# AD8367_AGC.net
KiCad netlist of a schematic drawn in Altium Designer
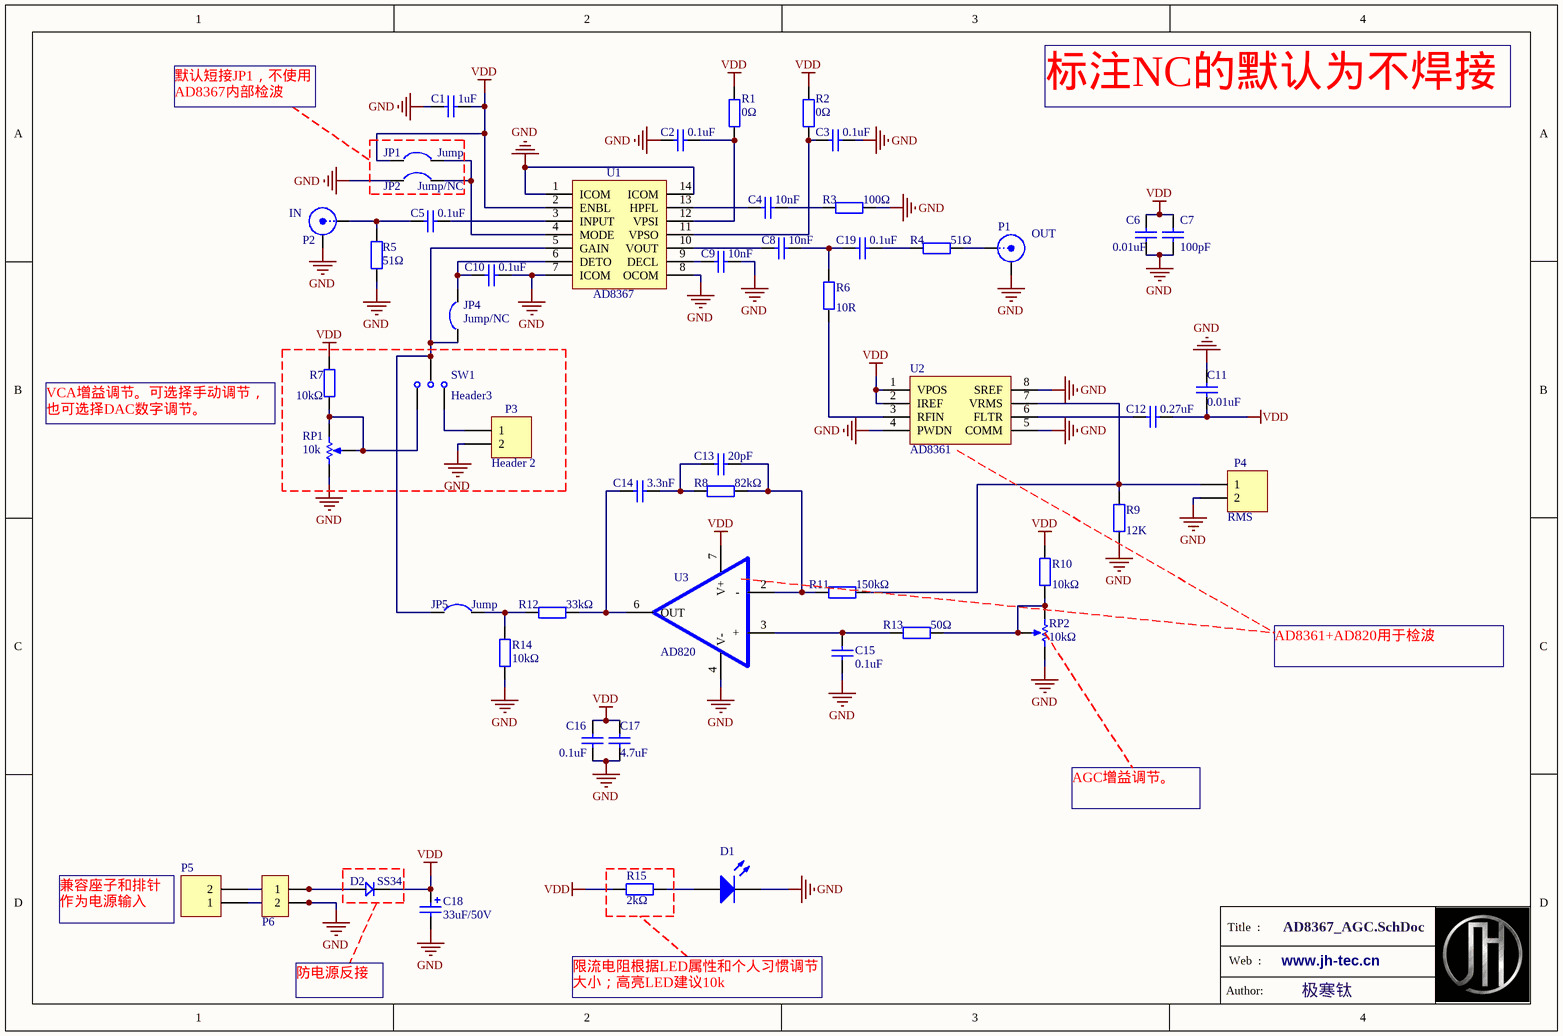
[diagram p0: AD8367_AGC.SchDoc]

(export (version "E")
  (design (tool "Eeschema 10.0.6"))
  (components
    (comp (ref "C1")
      (value "1uF")
      (footprint "JH_PCB:C0603")
      (description "Capacitor (Semiconductor SIM Model)")
      (fields (field (name "PUBLISHER") "Altium Limited"))
      (libsource (lib "mylib") (part "Cap Semi"))
    )
    (comp (ref "C2")
      (value "0.1uF")
      (footprint "JH_PCB:C0603")
      (description "Capacitor (Semiconductor SIM Model)")
      (fields (field (name "PUBLISHER") "Altium Limited"))
      (libsource (lib "mylib") (part "Cap Semi"))
    )
    (comp (ref "C3")
      (value "0.1uF")
      (footprint "JH_PCB:C0603")
      (description "Capacitor (Semiconductor SIM Model)")
      (fields (field (name "PUBLISHER") "Altium Limited"))
      (libsource (lib "mylib") (part "Cap Semi"))
    )
    (comp (ref "C4")
      (value "10nF")
      (footprint "JH_PCB:C0603")
      (description "Capacitor (Semiconductor SIM Model)")
      (fields (field (name "PUBLISHER") "Altium Limited"))
      (libsource (lib "mylib") (part "Cap Semi"))
    )
    (comp (ref "C5")
      (value "0.1uF")
      (footprint "JH_PCB:C0603")
      (description "Capacitor (Semiconductor SIM Model)")
      (fields (field (name "PUBLISHER") "Altium Limited"))
      (libsource (lib "mylib") (part "Cap Semi"))
    )
    (comp (ref "C6")
      (value "0.01uF")
      (footprint "JH_PCB:C0603")
      (description "Capacitor (Semiconductor SIM Model)")
      (fields (field (name "PUBLISHER") "Altium Limited"))
      (libsource (lib "mylib") (part "Cap Semi"))
    )
    (comp (ref "C7")
      (value "100pF")
      (footprint "JH_PCB:C0603")
      (description "Capacitor (Semiconductor SIM Model)")
      (fields (field (name "PUBLISHER") "Altium Limited"))
      (libsource (lib "mylib") (part "Cap Semi"))
    )
    (comp (ref "C8")
      (value "10nF")
      (footprint "JH_PCB:C0603")
      (description "Capacitor (Semiconductor SIM Model)")
      (fields (field (name "PUBLISHER") "Altium Limited"))
      (libsource (lib "mylib") (part "Cap Semi"))
    )
    (comp (ref "C9")
      (value "10nF")
      (footprint "JH_PCB:C0603")
      (description "Capacitor (Semiconductor SIM Model)")
      (fields (field (name "PUBLISHER") "Altium Limited"))
      (libsource (lib "mylib") (part "Cap Semi"))
    )
    (comp (ref "C10")
      (value "0.1uF")
      (footprint "JH_PCB:C0603")
      (description "Capacitor (Semiconductor SIM Model)")
      (fields (field (name "PUBLISHER") "Altium Limited"))
      (libsource (lib "mylib") (part "Cap Semi"))
    )
    (comp (ref "C11")
      (value "0.01uF")
      (footprint "JH_PCB:C0603")
      (description "Capacitor (Semiconductor SIM Model)")
      (fields (field (name "PUBLISHER") "Altium Limited"))
      (libsource (lib "mylib") (part "Cap Semi"))
    )
    (comp (ref "C12")
      (value "0.27uF")
      (footprint "JH_PCB:C0603")
      (description "Capacitor (Semiconductor SIM Model)")
      (fields (field (name "PUBLISHER") "Altium Limited"))
      (libsource (lib "mylib") (part "Cap Semi"))
    )
    (comp (ref "C13")
      (value "20pF")
      (footprint "JH_PCB:C0603")
      (description "Capacitor (Semiconductor SIM Model)")
      (fields (field (name "PUBLISHER") "Altium Limited"))
      (libsource (lib "mylib") (part "Cap Semi"))
    )
    (comp (ref "C14")
      (value "3.3nF")
      (footprint "JH_PCB:C0603")
      (description "Capacitor (Semiconductor SIM Model)")
      (fields (field (name "PUBLISHER") "Altium Limited"))
      (libsource (lib "mylib") (part "Cap Semi"))
    )
    (comp (ref "C15")
      (value "0.1uF")
      (footprint "JH_PCB:C0603")
      (description "Capacitor (Semiconductor SIM Model)")
      (fields (field (name "PUBLISHER") "Altium Limited"))
      (libsource (lib "mylib") (part "Cap Semi"))
    )
    (comp (ref "C16")
      (value "0.1uF")
      (footprint "JH_PCB:C0603")
      (description "Capacitor (Semiconductor SIM Model)")
      (fields (field (name "PUBLISHER") "Altium Limited"))
      (libsource (lib "mylib") (part "Cap Semi"))
    )
    (comp (ref "C17")
      (value "4.7uF")
      (footprint "JH_PCB:C0805")
      (description "Capacitor (Semiconductor SIM Model)")
      (fields (field (name "PUBLISHER") "Altium Limited"))
      (libsource (lib "mylib") (part "Cap Semi"))
    )
    (comp (ref "C18")
      (value "33uF/50V")
      (footprint "JH_PCB:C6.3*7.7")
      (description "Polarized Capacitor (Surface Mount)")
      (fields (field (name "PUBLISHER") "Altium Limited"))
      (libsource (lib "mylib") (part "Cap Pol3_1"))
    )
    (comp (ref "C19")
      (value "0.1uF")
      (footprint "JH_PCB:C0603")
      (description "Capacitor (Semiconductor SIM Model)")
      (fields (field (name "PUBLISHER") "Altium Limited"))
      (libsource (lib "mylib") (part "Cap Semi"))
    )
    (comp (ref "D1")
      (value "LED3")
      (footprint "JH_PCB:LED_GREEN_0603")
      (description "Typical BLUE SiC LED")
      (fields (field (name "PUBLISHER") "Altium Limited"))
      (libsource (lib "mylib") (part "LED3"))
    )
    (comp (ref "D2")
      (value "SS34")
      (footprint "JH_PCB:DO-214AC")
      (description "1N4148")
      (libsource (lib "ATK-SIM900A") (part "D"))
    )
    (comp (ref "JP1") (value "Jump") (footprint "JH_PCB:JUMP") (libsource (lib "") (part "Jump_1")))
    (comp (ref "JP2") (value "Jump/NC") (footprint "JH_PCB:JUMP") (libsource (lib "") (part "Jump_1")))
    (comp (ref "JP4") (value "Jump/NC") (footprint "JH_PCB:JUMP") (libsource (lib "常用sch") (part "Jump")))
    (comp (ref "JP5") (value "Jump") (footprint "JH_PCB:JUMP") (libsource (lib "") (part "Jump_1")))
    (comp (ref "P1") (value "OUT") (footprint "JH_PCB:SMA_3D") (libsource (lib "常用sch") (part "SMA")))
    (comp (ref "P2") (value "IN") (footprint "JH_PCB:SMA_3D") (libsource (lib "常用sch") (part "SMA")))
    (comp (ref "P3")
      (value "Header 2")
      (footprint "JH_PCB:HDR1X2")
      (description "Header, 2-Pin")
      (fields (field (name "PUBLISHER") "Altium Limited"))
      (libsource (lib "Miscellaneous Connectors") (part "Header 2"))
    )
    (comp (ref "P4")
      (value "RMS")
      (footprint "JH_PCB:HDR1X2")
      (description "Header, 2-Pin")
      (fields (field (name "PUBLISHER") "Altium Limited"))
      (libsource (lib "Miscellaneous Connectors") (part "Header 2"))
    )
    (comp (ref "P5")
      (value "~")
      (footprint "JH_PCB:HDR1X2")
      (description "Header, 2-Pin")
      (fields (field (name "PUBLISHER") "Altium Limited"))
      (libsource (lib "") (part "Header 2_1"))
    )
    (comp (ref "P6")
      (value "HDR-1X2")
      (footprint "VH3.96-LI-2P")
      (description "2P接插件")
      (fields (field (name "版权归属") "源创客"))
      (libsource (lib "4.8   - 接插件-脚距3.96") (part "Header 2"))
    )
    (comp (ref "R1")
      (value "0Ω")
      (footprint "JH_PCB:R0603")
      (description "Resistor")
      (fields (field (name "PUBLISHER") "Altium Limited"))
      (libsource (lib "") (part "Res2_1"))
    )
    (comp (ref "R2")
      (value "0Ω")
      (footprint "JH_PCB:R0603")
      (description "Resistor")
      (fields (field (name "PUBLISHER") "Altium Limited"))
      (libsource (lib "") (part "Res2_1"))
    )
    (comp (ref "R3")
      (value "100Ω")
      (footprint "JH_PCB:R0603")
      (description "Resistor")
      (fields (field (name "PUBLISHER") "Altium Limited"))
      (libsource (lib "Miscellaneous Devices") (part "Res2"))
    )
    (comp (ref "R4")
      (value "51Ω")
      (footprint "JH_PCB:R0603")
      (description "Resistor")
      (fields (field (name "PUBLISHER") "Altium Limited"))
      (libsource (lib "Miscellaneous Devices") (part "Res2"))
    )
    (comp (ref "R5")
      (value "51Ω")
      (footprint "JH_PCB:R0603")
      (description "Resistor")
      (fields (field (name "PUBLISHER") "Altium Limited"))
      (libsource (lib "") (part "Res2_1"))
    )
    (comp (ref "R6")
      (value "10R")
      (footprint "JH_PCB:R0603")
      (description "Resistor")
      (fields (field (name "PUBLISHER") "Altium Limited"))
      (libsource (lib "") (part "Res2_1"))
    )
    (comp (ref "R7")
      (value "10kΩ")
      (footprint "JH_PCB:R0603")
      (description "Resistor")
      (fields (field (name "PUBLISHER") "Altium Limited"))
      (libsource (lib "") (part "Res2_1"))
    )
    (comp (ref "R8")
      (value "82kΩ")
      (footprint "JH_PCB:R0603")
      (description "Resistor")
      (fields (field (name "PUBLISHER") "Altium Limited"))
      (libsource (lib "Miscellaneous Devices") (part "Res2"))
    )
    (comp (ref "R9")
      (value "12K")
      (footprint "JH_PCB:R0603")
      (description "Resistor")
      (fields (field (name "PUBLISHER") "Altium Limited"))
      (libsource (lib "") (part "Res2_1"))
    )
    (comp (ref "R10")
      (value "10kΩ")
      (footprint "JH_PCB:R0603")
      (description "Resistor")
      (fields (field (name "PUBLISHER") "Altium Limited"))
      (libsource (lib "") (part "Res2_1"))
    )
    (comp (ref "R11")
      (value "150kΩ")
      (footprint "JH_PCB:R0603")
      (description "Resistor")
      (fields (field (name "PUBLISHER") "Altium Limited"))
      (libsource (lib "Miscellaneous Devices") (part "Res2"))
    )
    (comp (ref "R12")
      (value "33kΩ")
      (footprint "JH_PCB:R0603")
      (description "Resistor")
      (fields (field (name "PUBLISHER") "Altium Limited"))
      (libsource (lib "Miscellaneous Devices") (part "Res2"))
    )
    (comp (ref "R13")
      (value "50Ω")
      (footprint "JH_PCB:R0603")
      (description "Resistor")
      (fields (field (name "PUBLISHER") "Altium Limited"))
      (libsource (lib "Miscellaneous Devices") (part "Res2"))
    )
    (comp (ref "R14")
      (value "10kΩ")
      (footprint "JH_PCB:R0603")
      (description "Resistor")
      (fields (field (name "PUBLISHER") "Altium Limited"))
      (libsource (lib "") (part "Res2_1"))
    )
    (comp (ref "R15")
      (value "2kΩ")
      (footprint "JH_PCB:R0603")
      (description "Resistor")
      (fields (field (name "PUBLISHER") "Altium Limited"))
      (libsource (lib "") (part "Res2_2"))
    )
    (comp (ref "RP1") (value "10k") (footprint "RP_3296W") (libsource (lib "常用sch") (part "SW_A")))
    (comp (ref "RP2") (value "10kΩ") (footprint "RP_3296W") (libsource (lib "常用sch") (part "SW_A")))
    (comp (ref "SW1") (value "Header3") (footprint "JH_PCB:HDR1X3") (libsource (lib "常用sch") (part "SW")))
    (comp (ref "U1") (value "AD8367") (footprint "JH_PCB:TSSOP14") (libsource (lib "常用sch") (part "AD8367")))
    (comp (ref "U2") (value "AD8361") (footprint "JH_PCB:MSOP8") (libsource (lib "常用sch") (part "AD8361")))
    (comp (ref "U3") (value "AD820") (footprint "JH_PCB:SOP-8") (libsource (lib "常用sch") (part "单运放1")))
  )
  (nets
    (net (code "1") (name "GND") (class "Default")
      (node (ref "C1") (pin "1") (pinfunction "1_1") (pintype "passive"))
      (node (ref "C10") (pin "2") (pinfunction "2_2") (pintype "passive"))
      (node (ref "C11") (pin "2") (pinfunction "2_2") (pintype "passive"))
      (node (ref "C15") (pin "2") (pinfunction "2_2") (pintype "passive"))
      (node (ref "C16") (pin "2") (pinfunction "2_2") (pintype "passive"))
      (node (ref "C17") (pin "1") (pinfunction "1_1") (pintype "passive"))
      (node (ref "C18") (pin "2") (pinfunction "2_2") (pintype "passive"))
      (node (ref "C2") (pin "1") (pinfunction "1_1") (pintype "passive"))
      (node (ref "C3") (pin "1") (pinfunction "1_1") (pintype "passive"))
      (node (ref "C6") (pin "2") (pinfunction "2_2") (pintype "passive"))
      (node (ref "C7") (pin "2") (pinfunction "2_2") (pintype "passive"))
      (node (ref "C9") (pin "2") (pinfunction "2_2") (pintype "passive"))
      (node (ref "D1") (pin "2") (pinfunction "K_2") (pintype "passive"))
      (node (ref "JP2") (pin "1") (pinfunction "1_1") (pintype "passive"))
      (node (ref "P1") (pin "2") (pinfunction "Y_2") (pintype "passive"))
      (node (ref "P2") (pin "2") (pinfunction "Y_2") (pintype "passive"))
      (node (ref "P3") (pin "2") (pinfunction "2_2") (pintype "passive"))
      (node (ref "P4") (pin "2") (pinfunction "2_2") (pintype "passive"))
      (node (ref "P5") (pin "1") (pinfunction "1_1") (pintype "passive"))
      (node (ref "P6") (pin "2") (pinfunction "2_2") (pintype "passive"))
      (node (ref "R14") (pin "2") (pinfunction "2_2") (pintype "passive"))
      (node (ref "R3") (pin "2") (pinfunction "2_2") (pintype "passive"))
      (node (ref "R5") (pin "2") (pinfunction "2_2") (pintype "passive"))
      (node (ref "R9") (pin "2") (pinfunction "2_2") (pintype "passive"))
      (node (ref "RP1") (pin "1") (pinfunction "TOP_1") (pintype "passive"))
      (node (ref "RP2") (pin "3") (pinfunction "BOT_3") (pintype "passive"))
      (node (ref "U1") (pin "1") (pinfunction "ICOM_1") (pintype "passive"))
      (node (ref "U1") (pin "14") (pinfunction "ICOM_14") (pintype "passive"))
      (node (ref "U1") (pin "7") (pinfunction "ICOM_7") (pintype "passive"))
      (node (ref "U1") (pin "8") (pinfunction "OCOM_8") (pintype "passive"))
      (node (ref "U2") (pin "4") (pinfunction "PWDN_4") (pintype "passive"))
      (node (ref "U2") (pin "5") (pinfunction "COMM_5") (pintype "passive"))
      (node (ref "U2") (pin "8") (pinfunction "SREF_8") (pintype "passive"))
      (node (ref "U3") (pin "4") (pinfunction "V-_4") (pintype "passive"))
    )
    (net (code "2") (name "Net-(C4-Pad2)") (class "Default")
      (node (ref "C4") (pin "2") (pinfunction "2_2") (pintype "passive"))
      (node (ref "R3") (pin "1") (pinfunction "1_1") (pintype "passive"))
    )
    (net (code "3") (name "Net-(C13-Pad1)") (class "Default")
      (node (ref "C13") (pin "1") (pinfunction "1_1") (pintype "passive"))
      (node (ref "C14") (pin "2") (pinfunction "2_2") (pintype "passive"))
      (node (ref "R8") (pin "1") (pinfunction "1_1") (pintype "passive"))
    )
    (net (code "4") (name "Net-(C19-Pad1)") (class "Default")
      (node (ref "C19") (pin "1") (pinfunction "1_1") (pintype "passive"))
      (node (ref "C8") (pin "2") (pinfunction "2_2") (pintype "passive"))
      (node (ref "R6") (pin "1") (pinfunction "1_1") (pintype "passive"))
    )
    (net (code "5") (name "Net-(C19-Pad2)") (class "Default")
      (node (ref "C19") (pin "2") (pinfunction "2_2") (pintype "passive"))
      (node (ref "R4") (pin "1") (pinfunction "1_1") (pintype "passive"))
    )
    (net (code "6") (name "Net-(D1-A)") (class "Default")
      (node (ref "D1") (pin "1") (pinfunction "A_1") (pintype "passive"))
      (node (ref "R15") (pin "1") (pinfunction "1_1") (pintype "passive"))
    )
    (net (code "7") (name "Net-(D2-Pad1)") (class "Default")
      (node (ref "D2") (pin "1") (pintype "passive"))
      (node (ref "P5") (pin "2") (pinfunction "2_2") (pintype "passive"))
      (node (ref "P6") (pin "1") (pinfunction "1_1") (pintype "passive"))
    )
    (net (code "8") (name "Net-(JP5-Pad2)") (class "Default")
      (node (ref "JP5") (pin "2") (pinfunction "2_2") (pintype "passive"))
      (node (ref "R12") (pin "1") (pinfunction "1_1") (pintype "passive"))
      (node (ref "R14") (pin "1") (pinfunction "1_1") (pintype "passive"))
    )
    (net (code "9") (name "Net-(P1-X)") (class "Default")
      (node (ref "P1") (pin "1") (pinfunction "X_1") (pintype "passive"))
      (node (ref "R4") (pin "2") (pinfunction "2_2") (pintype "passive"))
    )
    (net (code "10") (name "Net-(P2-X)") (class "Default")
      (node (ref "C5") (pin "1") (pinfunction "1_1") (pintype "passive"))
      (node (ref "P2") (pin "1") (pinfunction "X_1") (pintype "passive"))
      (node (ref "R5") (pin "1") (pinfunction "1_1") (pintype "passive"))
    )
    (net (code "11") (name "Net-(P3-Pad1)") (class "Default")
      (node (ref "P3") (pin "1") (pinfunction "1_1") (pintype "passive"))
      (node (ref "SW1") (pin "1") (pinfunction "1_1") (pintype "passive"))
    )
    (net (code "12") (name "Net-(RP1-BOT)") (class "Default")
      (node (ref "R7") (pin "2") (pinfunction "2_2") (pintype "passive"))
      (node (ref "RP1") (pin "2") (pinfunction "TAP_2") (pintype "passive"))
      (node (ref "RP1") (pin "3") (pinfunction "BOT_3") (pintype "passive"))
      (node (ref "SW1") (pin "3") (pinfunction "3_3") (pintype "passive"))
    )
    (net (code "13") (name "Net-(RP2-TAP)") (class "Default")
      (node (ref "R10") (pin "2") (pinfunction "2_2") (pintype "passive"))
      (node (ref "R13") (pin "2") (pinfunction "2_2") (pintype "passive"))
      (node (ref "RP2") (pin "1") (pinfunction "TOP_1") (pintype "passive"))
      (node (ref "RP2") (pin "2") (pinfunction "TAP_2") (pintype "passive"))
    )
    (net (code "14") (name "Net-(U1-DECL)") (class "Default")
      (node (ref "C9") (pin "1") (pinfunction "1_1") (pintype "passive"))
      (node (ref "U1") (pin "9") (pinfunction "DECL_9") (pintype "passive"))
    )
    (net (code "15") (name "Net-(U1-DETO)") (class "Default")
      (node (ref "C10") (pin "1") (pinfunction "1_1") (pintype "passive"))
      (node (ref "JP4") (pin "2") (pinfunction "2_2") (pintype "passive"))
      (node (ref "U1") (pin "6") (pinfunction "DETO_6") (pintype "passive"))
    )
    (net (code "16") (name "Net-(U1-GAIN)") (class "Default")
      (node (ref "JP4") (pin "1") (pinfunction "1_1") (pintype "passive"))
      (node (ref "JP5") (pin "1") (pinfunction "1_1") (pintype "passive"))
      (node (ref "SW1") (pin "2") (pinfunction "2_2") (pintype "passive"))
      (node (ref "U1") (pin "5") (pinfunction "GAIN_5") (pintype "passive"))
    )
    (net (code "17") (name "Net-(U1-HPFL)") (class "Default")
      (node (ref "C4") (pin "1") (pinfunction "1_1") (pintype "passive"))
      (node (ref "U1") (pin "13") (pinfunction "HPFL_13") (pintype "passive"))
    )
    (net (code "18") (name "Net-(U1-INPUT)") (class "Default")
      (node (ref "C5") (pin "2") (pinfunction "2_2") (pintype "passive"))
      (node (ref "U1") (pin "3") (pinfunction "INPUT_3") (pintype "passive"))
    )
    (net (code "19") (name "Net-(U1-MODE)") (class "Default")
      (node (ref "JP1") (pin "2") (pinfunction "2_2") (pintype "passive"))
      (node (ref "JP2") (pin "2") (pinfunction "2_2") (pintype "passive"))
      (node (ref "U1") (pin "4") (pinfunction "MODE_4") (pintype "passive"))
    )
    (net (code "20") (name "Net-(U1-VOUT)") (class "Default")
      (node (ref "C8") (pin "1") (pinfunction "1_1") (pintype "passive"))
      (node (ref "U1") (pin "10") (pinfunction "VOUT_10") (pintype "passive"))
    )
    (net (code "21") (name "Net-(U1-VPSI)") (class "Default")
      (node (ref "C2") (pin "2") (pinfunction "2_2") (pintype "passive"))
      (node (ref "R1") (pin "2") (pinfunction "2_2") (pintype "passive"))
      (node (ref "U1") (pin "12") (pinfunction "VPSI_12") (pintype "passive"))
    )
    (net (code "22") (name "Net-(U1-VPSO)") (class "Default")
      (node (ref "C3") (pin "2") (pinfunction "2_2") (pintype "passive"))
      (node (ref "R2") (pin "2") (pinfunction "2_2") (pintype "passive"))
      (node (ref "U1") (pin "11") (pinfunction "VPSO_11") (pintype "passive"))
    )
    (net (code "23") (name "Net-(U2-FLTR)") (class "Default")
      (node (ref "C12") (pin "1") (pinfunction "1_1") (pintype "passive"))
      (node (ref "U2") (pin "6") (pinfunction "FLTR_6") (pintype "passive"))
    )
    (net (code "24") (name "Net-(U2-RFIN)") (class "Default")
      (node (ref "R6") (pin "2") (pinfunction "2_2") (pintype "passive"))
      (node (ref "U2") (pin "3") (pinfunction "RFIN_3") (pintype "passive"))
    )
    (net (code "25") (name "Net-(U2-VRMS)") (class "Default")
      (node (ref "P4") (pin "1") (pinfunction "1_1") (pintype "passive"))
      (node (ref "R11") (pin "2") (pinfunction "2_2") (pintype "passive"))
      (node (ref "R9") (pin "1") (pinfunction "1_1") (pintype "passive"))
      (node (ref "U2") (pin "7") (pinfunction "VRMS_7") (pintype "passive"))
    )
    (net (code "26") (name "Net-(U3-+)") (class "Default")
      (node (ref "C15") (pin "1") (pinfunction "1_1") (pintype "passive"))
      (node (ref "R13") (pin "1") (pinfunction "1_1") (pintype "passive"))
      (node (ref "U3") (pin "3") (pinfunction "+_3") (pintype "passive"))
    )
    (net (code "27") (name "Net-(U3--)") (class "Default")
      (node (ref "C13") (pin "2") (pinfunction "2_2") (pintype "passive"))
      (node (ref "R11") (pin "1") (pinfunction "1_1") (pintype "passive"))
      (node (ref "R8") (pin "2") (pinfunction "2_2") (pintype "passive"))
      (node (ref "U3") (pin "2") (pinfunction "-_2") (pintype "passive"))
    )
    (net (code "28") (name "Net-(U3-OUT)") (class "Default")
      (node (ref "C14") (pin "1") (pinfunction "1_1") (pintype "passive"))
      (node (ref "R12") (pin "2") (pinfunction "2_2") (pintype "passive"))
      (node (ref "U3") (pin "6") (pinfunction "OUT_6") (pintype "passive"))
    )
    (net (code "29") (name "VDD") (class "Default")
      (node (ref "C1") (pin "2") (pinfunction "2_2") (pintype "passive"))
      (node (ref "C11") (pin "1") (pinfunction "1_1") (pintype "passive"))
      (node (ref "C12") (pin "2") (pinfunction "2_2") (pintype "passive"))
      (node (ref "C16") (pin "1") (pinfunction "1_1") (pintype "passive"))
      (node (ref "C17") (pin "2") (pinfunction "2_2") (pintype "passive"))
      (node (ref "C18") (pin "1") (pinfunction "1_1") (pintype "passive"))
      (node (ref "C6") (pin "1") (pinfunction "1_1") (pintype "passive"))
      (node (ref "C7") (pin "1") (pinfunction "1_1") (pintype "passive"))
      (node (ref "D2") (pin "2") (pintype "passive"))
      (node (ref "JP1") (pin "1") (pinfunction "1_1") (pintype "passive"))
      (node (ref "R1") (pin "1") (pinfunction "1_1") (pintype "passive"))
      (node (ref "R10") (pin "1") (pinfunction "1_1") (pintype "passive"))
      (node (ref "R15") (pin "2") (pinfunction "2_2") (pintype "passive"))
      (node (ref "R2") (pin "1") (pinfunction "1_1") (pintype "passive"))
      (node (ref "R7") (pin "1") (pinfunction "1_1") (pintype "passive"))
      (node (ref "U1") (pin "2") (pinfunction "ENBL_2") (pintype "passive"))
      (node (ref "U2") (pin "1") (pinfunction "VPOS_1") (pintype "passive"))
      (node (ref "U2") (pin "2") (pinfunction "IREF_2") (pintype "passive"))
      (node (ref "U3") (pin "7") (pinfunction "V+_7") (pintype "passive"))
    )
  )
)
